# Project_2.net
KiCad netlist of a schematic drawn in EAGLE
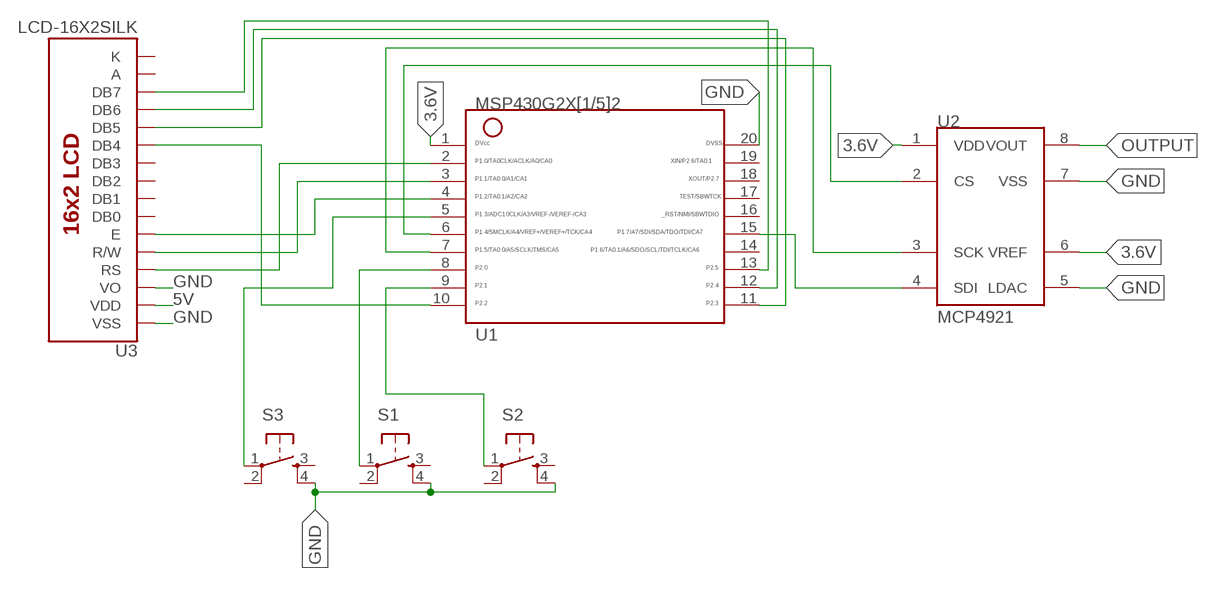
[diagram p0: schematic, sheet 1]

(export (version "E")
  (design (tool "Eeschema 10.0.6"))
  (components
    (comp (ref "S1")
      (value "TAC_SWITCHPTH")
      (footprint "eagle-import:TACTILE-PTH")
      (libsource (lib "eagle-import") (part "TAC_SWITCHPTH"))
    )
    (comp (ref "S2")
      (value "TAC_SWITCHPTH")
      (footprint "eagle-import:TACTILE-PTH")
      (libsource (lib "eagle-import") (part "TAC_SWITCHPTH"))
    )
    (comp (ref "S3")
      (value "TAC_SWITCHPTH")
      (footprint "eagle-import:TACTILE-PTH")
      (libsource (lib "eagle-import") (part "TAC_SWITCHPTH"))
    )
    (comp (ref "U1")
      (value "G2X[1/5]2---PW20")
      (footprint "eagle-import:PW20")
      (libsource (lib "eagle-import") (part "G2X[1/5]2---PW20"))
    )
    (comp (ref "U2")
      (value "MCP4921")
      (footprint "eagle-import:DIL8")
      (libsource (lib "eagle-import") (part "MCP4921"))
    )
    (comp (ref "U3")
      (value "LCD-16X2SILK")
      (footprint "eagle-import:LCD-16X2")
      (libsource (lib "eagle-import") (part "LCD-16X2SILK"))
    )
  )
  (nets
    (net (code "1") (name "/5V") (class "Default")
      (node (ref "U3") (pin "2") (pinfunction "VDD_2") (pintype "power_in"))
    )
    (net (code "2") (name "/A") (class "Default")
      (node (ref "U3") (pin "15") (pinfunction "A_15") (pintype "power_in"))
    )
    (net (code "3") (name "/K") (class "Default")
      (node (ref "U3") (pin "16") (pinfunction "K_16") (pintype "power_in"))
    )
    (net (code "4") (name "3.6V") (class "Default")
      (node (ref "U1") (pin "1") (pinfunction "1_1") (pintype "bidirectional"))
      (node (ref "U2") (pin "1") (pinfunction "VDD_1") (pintype "bidirectional"))
      (node (ref "U2") (pin "6") (pinfunction "VREF_6") (pintype "bidirectional"))
    )
    (net (code "5") (name "GND") (class "Default")
      (node (ref "S1") (pin "4") (pinfunction "4_4") (pintype "passive"))
      (node (ref "S2") (pin "4") (pinfunction "4_4") (pintype "passive"))
      (node (ref "S3") (pin "4") (pinfunction "4_4") (pintype "passive"))
      (node (ref "U1") (pin "20") (pinfunction "20_20") (pintype "bidirectional"))
      (node (ref "U2") (pin "5") (pinfunction "LDAC_5") (pintype "bidirectional"))
      (node (ref "U2") (pin "7") (pinfunction "VSS_7") (pintype "bidirectional"))
      (node (ref "U3") (pin "1") (pinfunction "VSS_1") (pintype "power_in"))
      (node (ref "U3") (pin "3") (pinfunction "VO_3") (pintype "bidirectional"))
    )
    (net (code "6") (name "Net-(S1-Pad1)") (class "Default")
      (node (ref "S1") (pin "1") (pinfunction "1_1") (pintype "passive"))
      (node (ref "U1") (pin "8") (pinfunction "8_8") (pintype "bidirectional"))
    )
    (net (code "7") (name "Net-(S2-Pad1)") (class "Default")
      (node (ref "S2") (pin "1") (pinfunction "1_1") (pintype "passive"))
      (node (ref "U1") (pin "9") (pinfunction "9_9") (pintype "bidirectional"))
    )
    (net (code "8") (name "Net-(S3-Pad1)") (class "Default")
      (node (ref "S3") (pin "1") (pinfunction "1_1") (pintype "passive"))
      (node (ref "U1") (pin "5") (pinfunction "5_5") (pintype "bidirectional"))
    )
    (net (code "9") (name "Net-(U2-CS)") (class "Default")
      (node (ref "U1") (pin "6") (pinfunction "6_6") (pintype "bidirectional"))
      (node (ref "U2") (pin "2") (pinfunction "CS_2") (pintype "bidirectional"))
    )
    (net (code "10") (name "Net-(U2-SCK)") (class "Default")
      (node (ref "U1") (pin "7") (pinfunction "7_7") (pintype "bidirectional"))
      (node (ref "U2") (pin "3") (pinfunction "SCK_3") (pintype "bidirectional"))
    )
    (net (code "11") (name "Net-(U2-SDI)") (class "Default")
      (node (ref "U1") (pin "15") (pinfunction "15_15") (pintype "bidirectional"))
      (node (ref "U2") (pin "4") (pinfunction "SDI_4") (pintype "bidirectional"))
    )
    (net (code "12") (name "Net-(U3-DB4)") (class "Default")
      (node (ref "U1") (pin "10") (pinfunction "10_10") (pintype "bidirectional"))
      (node (ref "U3") (pin "11") (pinfunction "DB4_11") (pintype "bidirectional"))
    )
    (net (code "13") (name "Net-(U3-DB5)") (class "Default")
      (node (ref "U1") (pin "11") (pinfunction "11_11") (pintype "bidirectional"))
      (node (ref "U3") (pin "12") (pinfunction "DB5_12") (pintype "bidirectional"))
    )
    (net (code "14") (name "Net-(U3-DB6)") (class "Default")
      (node (ref "U1") (pin "12") (pinfunction "12_12") (pintype "bidirectional"))
      (node (ref "U3") (pin "13") (pinfunction "DB6_13") (pintype "bidirectional"))
    )
    (net (code "15") (name "Net-(U3-DB7)") (class "Default")
      (node (ref "U1") (pin "13") (pinfunction "13_13") (pintype "bidirectional"))
      (node (ref "U3") (pin "14") (pinfunction "DB7_14") (pintype "bidirectional"))
    )
    (net (code "16") (name "Net-(U3-E)") (class "Default")
      (node (ref "U1") (pin "4") (pinfunction "4_4") (pintype "bidirectional"))
      (node (ref "U3") (pin "6") (pinfunction "E_6") (pintype "input"))
    )
    (net (code "17") (name "Net-(U3-RS)") (class "Default")
      (node (ref "U1") (pin "2") (pinfunction "2_2") (pintype "bidirectional"))
      (node (ref "U3") (pin "4") (pinfunction "RS_4") (pintype "input"))
    )
    (net (code "18") (name "Net-(U3-R{slash}W)") (class "Default")
      (node (ref "U1") (pin "3") (pinfunction "3_3") (pintype "bidirectional"))
      (node (ref "U3") (pin "5") (pinfunction "R/W_5") (pintype "input"))
    )
    (net (code "19") (name "OUTPUT") (class "Default")
      (node (ref "U2") (pin "8") (pinfunction "VOUT_8") (pintype "bidirectional"))
    )
    (net (code "20") (name "unconnected-(S1-Pad2)") (class "Default")
      (node (ref "S1") (pin "2") (pinfunction "2_2") (pintype "passive"))
    )
    (net (code "21") (name "unconnected-(S1-Pad3)") (class "Default")
      (node (ref "S1") (pin "3") (pinfunction "3_3") (pintype "passive"))
    )
    (net (code "22") (name "unconnected-(S2-Pad2)") (class "Default")
      (node (ref "S2") (pin "2") (pinfunction "2_2") (pintype "passive"))
    )
    (net (code "23") (name "unconnected-(S2-Pad3)") (class "Default")
      (node (ref "S2") (pin "3") (pinfunction "3_3") (pintype "passive"))
    )
    (net (code "24") (name "unconnected-(S3-Pad2)") (class "Default")
      (node (ref "S3") (pin "2") (pinfunction "2_2") (pintype "passive"))
    )
    (net (code "25") (name "unconnected-(S3-Pad3)") (class "Default")
      (node (ref "S3") (pin "3") (pinfunction "3_3") (pintype "passive"))
    )
    (net (code "26") (name "unconnected-(U1-Pad14)") (class "Default")
      (node (ref "U1") (pin "14") (pinfunction "14_14") (pintype "bidirectional"))
    )
    (net (code "27") (name "unconnected-(U1-Pad16)") (class "Default")
      (node (ref "U1") (pin "16") (pinfunction "16_16") (pintype "bidirectional"))
    )
    (net (code "28") (name "unconnected-(U1-Pad17)") (class "Default")
      (node (ref "U1") (pin "17") (pinfunction "17_17") (pintype "bidirectional"))
    )
    (net (code "29") (name "unconnected-(U1-Pad18)") (class "Default")
      (node (ref "U1") (pin "18") (pinfunction "18_18") (pintype "bidirectional"))
    )
    (net (code "30") (name "unconnected-(U1-Pad19)") (class "Default")
      (node (ref "U1") (pin "19") (pinfunction "19_19") (pintype "bidirectional"))
    )
    (net (code "31") (name "unconnected-(U3-DB0-Pad7)") (class "Default")
      (node (ref "U3") (pin "7") (pinfunction "DB0_7") (pintype "bidirectional"))
    )
    (net (code "32") (name "unconnected-(U3-DB1-Pad8)") (class "Default")
      (node (ref "U3") (pin "8") (pinfunction "DB1_8") (pintype "bidirectional"))
    )
    (net (code "33") (name "unconnected-(U3-DB2-Pad9)") (class "Default")
      (node (ref "U3") (pin "9") (pinfunction "DB2_9") (pintype "bidirectional"))
    )
    (net (code "34") (name "unconnected-(U3-DB3-Pad10)") (class "Default")
      (node (ref "U3") (pin "10") (pinfunction "DB3_10") (pintype "bidirectional"))
    )
  )
)
